# HABduino3_0.net
KiCad netlist of a schematic drawn in EAGLE
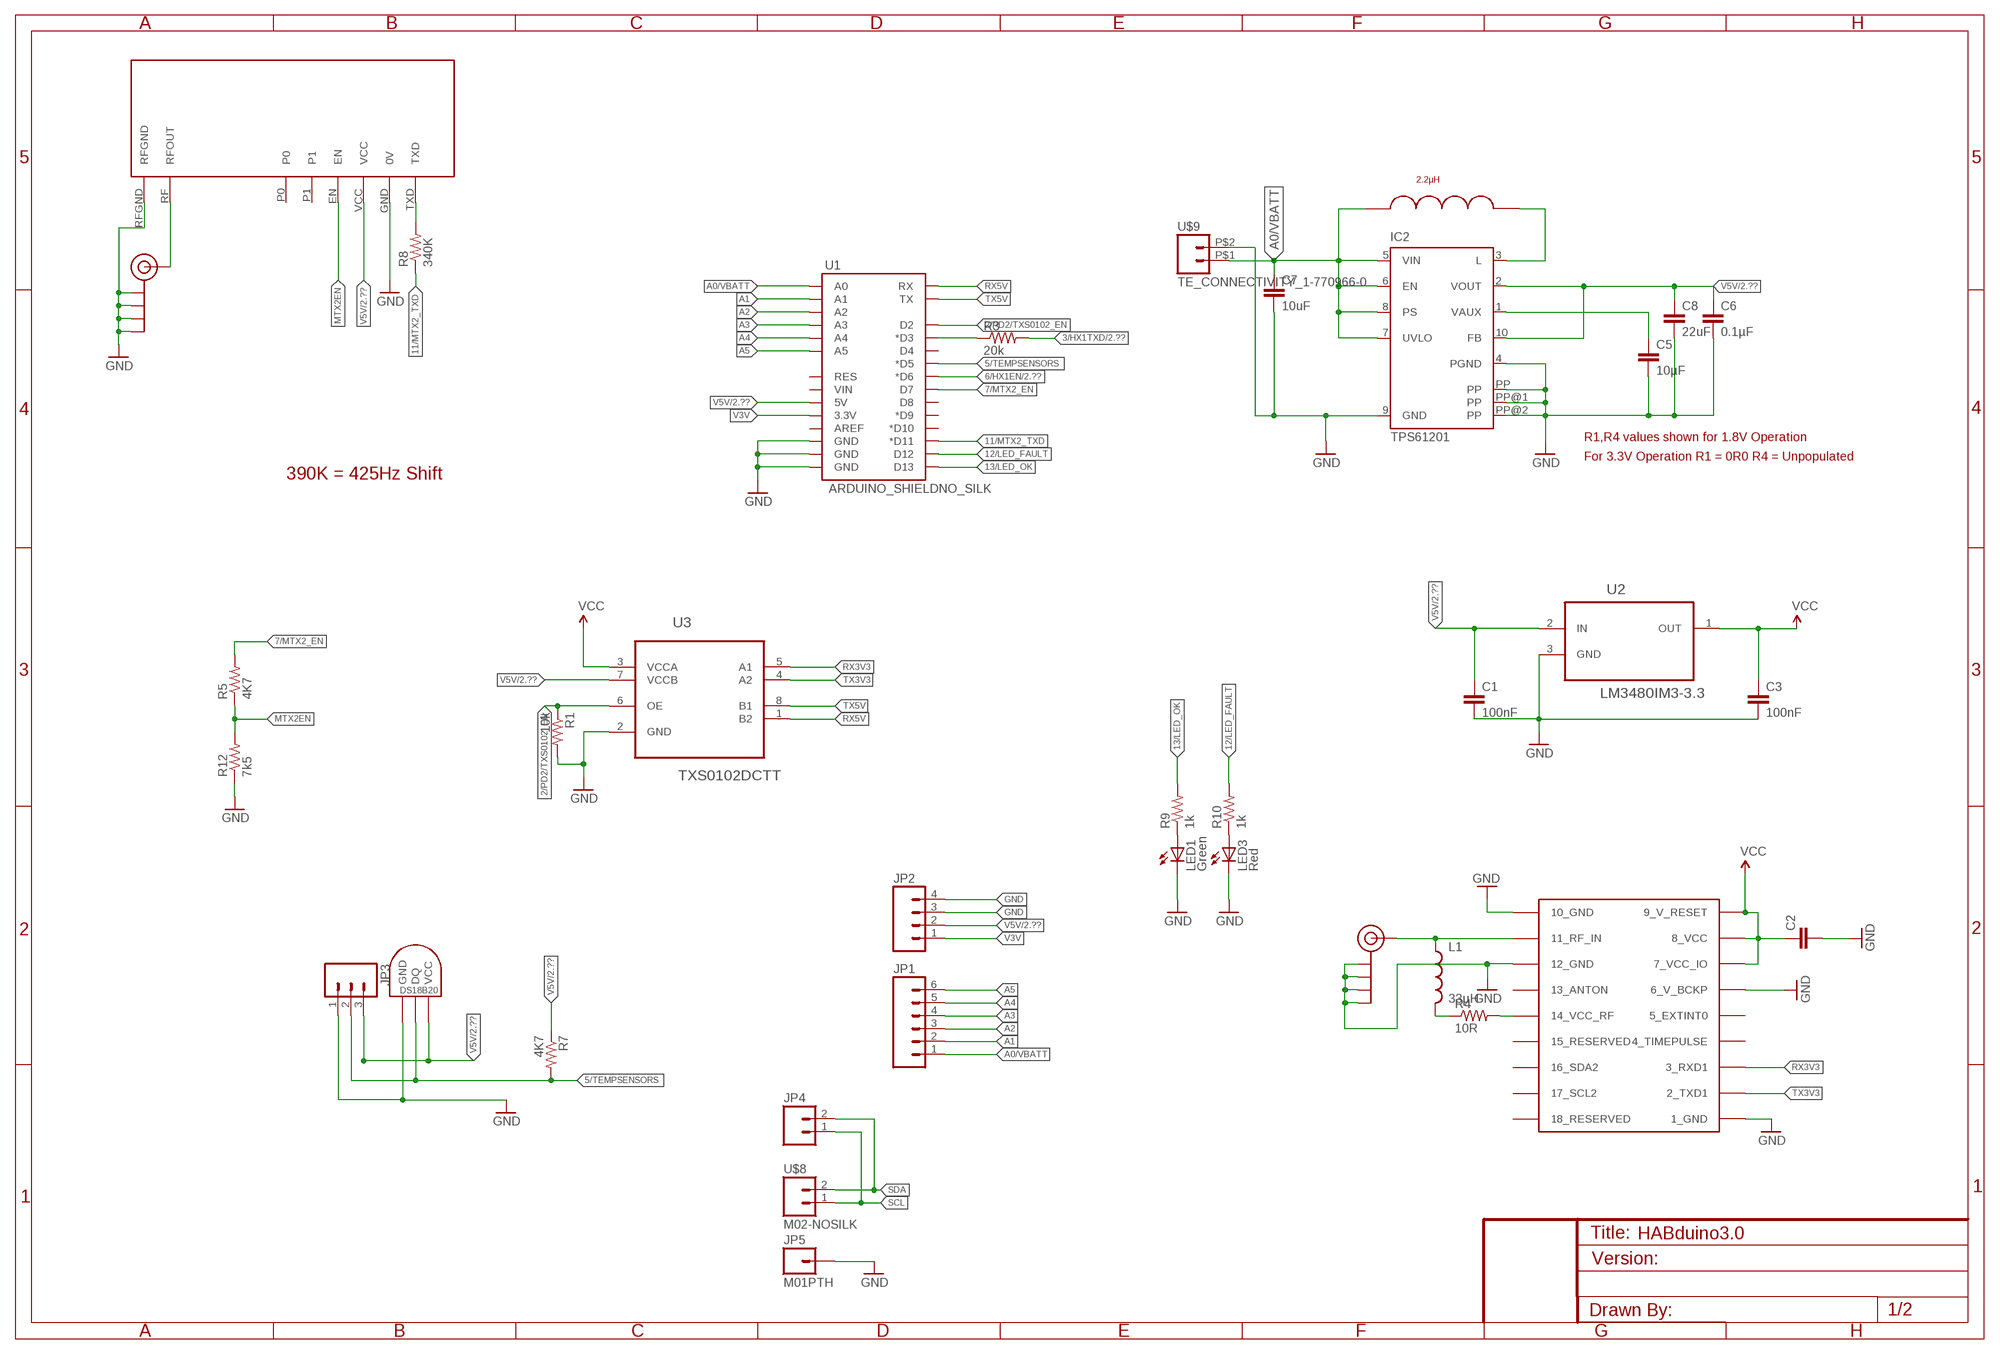
[diagram p0: schematic, sheet 1]
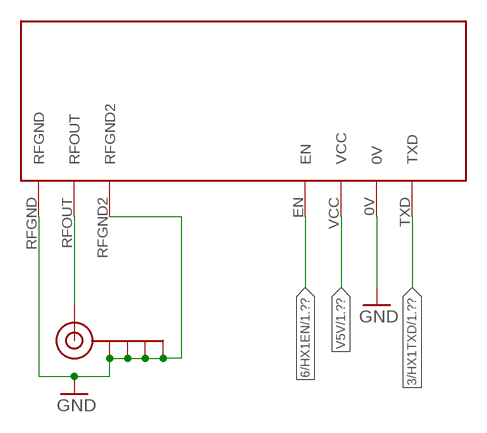
[diagram p1: schematic, sheet 2]

(export (version "E")
  (design (tool "Eeschema 10.0.6"))
  (components
    (comp (ref "J$3")
      (value "SMA_EDGE")
      (footprint "eagle-import:SMA-EDGE")
      (libsource (lib "eagle-import") (part "SMA_EDGE"))
    )
    (comp (ref "U$7")
      (value "RADIOMETRIX-HX1")
      (footprint "eagle-import:RADIOMETRIX-HX1")
      (libsource (lib "eagle-import") (part "RADIOMETRIX-HX1"))
    )
    (comp (ref "C1")
      (value "100nF")
      (footprint "eagle-import:0603-CAP")
      (libsource (lib "eagle-import") (part "CAP0603-CAP"))
    )
    (comp (ref "C2")
      (value "CAP0603-CAP")
      (footprint "eagle-import:0603-CAP")
      (libsource (lib "eagle-import") (part "CAP0603-CAP"))
    )
    (comp (ref "C3")
      (value "100nF")
      (footprint "eagle-import:0603-CAP")
      (libsource (lib "eagle-import") (part "CAP0603-CAP"))
    )
    (comp (ref "C5")
      (value "10µF")
      (footprint "eagle-import:0603-CAP")
      (libsource (lib "eagle-import") (part "CAP0603-CAP"))
    )
    (comp (ref "C6")
      (value "0.1µF")
      (footprint "eagle-import:0603-CAP")
      (libsource (lib "eagle-import") (part "CAP0603-CAP"))
    )
    (comp (ref "C7")
      (value "10uF")
      (footprint "eagle-import:1206")
      (libsource (lib "eagle-import") (part "CAP1206"))
    )
    (comp (ref "C8")
      (value "22uF")
      (footprint "eagle-import:1206")
      (libsource (lib "eagle-import") (part "CAP1206"))
    )
    (comp (ref "IC2")
      (value "TPS61201")
      (footprint "eagle-import:S-PDSO-N10")
      (fields (field (name "MPN") "TPS61201DRCT"))
      (libsource (lib "eagle-import") (part "TPS61201"))
    )
    (comp (ref "J$1")
      (value "SMA_EDGE")
      (footprint "eagle-import:SMA-EDGE")
      (libsource (lib "eagle-import") (part "SMA_EDGE"))
    )
    (comp (ref "J$2")
      (value "SMA_EDGE")
      (footprint "eagle-import:SMA-EDGE")
      (libsource (lib "eagle-import") (part "SMA_EDGE"))
    )
    (comp (ref "JP1")
      (value "M06SIP")
      (footprint "eagle-import:1X06")
      (libsource (lib "eagle-import") (part "M06SIP"))
    )
    (comp (ref "JP2")
      (value "M04PTH")
      (footprint "eagle-import:1X04")
      (libsource (lib "eagle-import") (part "M04PTH"))
    )
    (comp (ref "JP3")
      (value "M03PTH")
      (footprint "eagle-import:1X03")
      (libsource (lib "eagle-import") (part "M03PTH"))
    )
    (comp (ref "JP4")
      (value "M02PTH")
      (footprint "eagle-import:1X02")
      (libsource (lib "eagle-import") (part "M02PTH"))
    )
    (comp (ref "JP5")
      (value "M01PTH")
      (footprint "eagle-import:1X01")
      (libsource (lib "eagle-import") (part "M01PTH"))
    )
    (comp (ref "L1")
      (value "33µH")
      (footprint "eagle-import:0603")
      (libsource (lib "eagle-import") (part "INDUCTOR0603"))
    )
    (comp (ref "LED1")
      (value "Green")
      (footprint "eagle-import:LED-0603")
      (libsource (lib "eagle-import") (part "LED0603"))
    )
    (comp (ref "LED3")
      (value "Red")
      (footprint "eagle-import:LED-0603")
      (libsource (lib "eagle-import") (part "LED0603"))
    )
    (comp (ref "LPS4018")
      (value "2.2µH")
      (footprint "eagle-import:COILCRAFT_LPS4018")
      (libsource (lib "eagle-import") (part "COILCRAFT_LPS4018"))
    )
    (comp (ref "R1")
      (value "10k")
      (footprint "eagle-import:0603-RES")
      (libsource (lib "eagle-import") (part "RESISTOR0603-RES"))
    )
    (comp (ref "R3")
      (value "20k")
      (footprint "eagle-import:0603-RES")
      (libsource (lib "eagle-import") (part "RESISTOR0603-RES"))
    )
    (comp (ref "R4")
      (value "10R")
      (footprint "eagle-import:0603-RES")
      (libsource (lib "eagle-import") (part "RESISTOR0603-RES"))
    )
    (comp (ref "R5")
      (value "4K7")
      (footprint "eagle-import:0603-RES")
      (libsource (lib "eagle-import") (part "RESISTOR0603-RES"))
    )
    (comp (ref "R7")
      (value "4K7")
      (footprint "eagle-import:0603-RES")
      (libsource (lib "eagle-import") (part "RESISTOR0603-RES"))
    )
    (comp (ref "R8")
      (value "340K")
      (footprint "eagle-import:0603-RES")
      (libsource (lib "eagle-import") (part "RESISTOR0603-RES"))
    )
    (comp (ref "R9")
      (value "1k")
      (footprint "eagle-import:0603-RES")
      (libsource (lib "eagle-import") (part "RESISTOR0603-RES"))
    )
    (comp (ref "R10")
      (value "1k")
      (footprint "eagle-import:0603-RES")
      (libsource (lib "eagle-import") (part "RESISTOR0603-RES"))
    )
    (comp (ref "R12")
      (value "7k5")
      (footprint "eagle-import:0603-RES")
      (libsource (lib "eagle-import") (part "RESISTOR0603-RES"))
    )
    (comp (ref "TEMP")
      (value "DS1821")
      (footprint "eagle-import:DS18B20_SOIC")
      (libsource (lib "eagle-import") (part "DS1820SOIC"))
    )
    (comp (ref "U$1")
      (value "UBLOX_MAX")
      (footprint "eagle-import:UBLOX_MAX")
      (libsource (lib "eagle-import") (part "UBLOX_MAX"))
    )
    (comp (ref "U$4")
      (value "RADIOMETRIX-MTX2")
      (footprint "eagle-import:RADIOMETRIX-MTX2")
      (libsource (lib "eagle-import") (part "RADIOMETRIX-MTX2"))
    )
    (comp (ref "U$8")
      (value "M02-NOSILK")
      (footprint "eagle-import:M02-NOSILK")
      (libsource (lib "eagle-import") (part "M02-NOSILK"))
    )
    (comp (ref "U$9")
      (value "TE_CONNECTIVITY_1-770966-0")
      (footprint "eagle-import:TE_CONNECTIVITY_1-770966-0")
      (libsource (lib "eagle-import") (part "TE_CONNECTIVITY_1-770966-0"))
    )
    (comp (ref "U1")
      (value "ARDUINO_SHIELDNO_SILK")
      (footprint "eagle-import:DUEMILANOVE_VIAS")
      (libsource (lib "eagle-import") (part "ARDUINO_SHIELDNO_SILK"))
    )
    (comp (ref "U2")
      (value "LM3480IM3-3.3")
      (footprint "eagle-import:SOT95P251X112-3N")
      (libsource (lib "eagle-import") (part "LM3480IM3-3.3"))
    )
    (comp (ref "U3")
      (value "TXS0102DCTT")
      (footprint "eagle-import:SOP65P400X130-8N")
      (libsource (lib "eagle-import") (part "TXS0102DCTT"))
    )
  )
  (nets
    (net (code "1") (name "2{slash}PD2{slash}TXS0102_EN") (class "Default")
      (node (ref "R1") (pin "1") (pinfunction "1_1") (pintype "passive"))
      (node (ref "U1") (pin "D2") (pinfunction "D2_D2") (pintype "bidirectional"))
      (node (ref "U3") (pin "6") (pinfunction "OE_6") (pintype "input"))
    )
    (net (code "2") (name "3{slash}HX1TXD") (class "Default")
      (node (ref "R3") (pin "2") (pinfunction "2_2") (pintype "passive"))
      (node (ref "U$7") (pin "TXD") (pinfunction "TXD_TXD") (pintype "bidirectional"))
    )
    (net (code "3") (name "5{slash}TEMPSENSORS") (class "Default")
      (node (ref "JP3") (pin "2") (pinfunction "2_2") (pintype "passive"))
      (node (ref "R7") (pin "2") (pinfunction "2_2") (pintype "passive"))
      (node (ref "TEMP") (pin "DQ") (pinfunction "DQ_DQ") (pintype "bidirectional"))
      (node (ref "U1") (pin "D5") (pinfunction "*D5_D5") (pintype "bidirectional"))
    )
    (net (code "4") (name "6{slash}HX1EN") (class "Default")
      (node (ref "U$7") (pin "EN") (pinfunction "EN_EN") (pintype "bidirectional"))
      (node (ref "U1") (pin "D6") (pinfunction "*D6_D6") (pintype "bidirectional"))
    )
    (net (code "5") (name "7{slash}MTX2_EN") (class "Default")
      (node (ref "R5") (pin "2") (pinfunction "2_2") (pintype "passive"))
      (node (ref "U1") (pin "D7") (pinfunction "D7_D7") (pintype "bidirectional"))
    )
    (net (code "6") (name "11{slash}MTX2_TXD") (class "Default")
      (node (ref "R8") (pin "1") (pinfunction "1_1") (pintype "passive"))
      (node (ref "U1") (pin "D11") (pinfunction "*D11_D11") (pintype "bidirectional"))
    )
    (net (code "7") (name "12{slash}LED_FAULT") (class "Default")
      (node (ref "R10") (pin "2") (pinfunction "2_2") (pintype "passive"))
      (node (ref "U1") (pin "D12") (pinfunction "D12_D12") (pintype "bidirectional"))
    )
    (net (code "8") (name "13{slash}LED_OK") (class "Default")
      (node (ref "R9") (pin "2") (pinfunction "2_2") (pintype "passive"))
      (node (ref "U1") (pin "D13") (pinfunction "D13_D13") (pintype "bidirectional"))
    )
    (net (code "9") (name "A0{slash}VBATT") (class "Default")
      (node (ref "C7") (pin "1") (pinfunction "1_1") (pintype "passive"))
      (node (ref "IC2") (pin "5") (pinfunction "VIN_5") (pintype "input"))
      (node (ref "IC2") (pin "6") (pinfunction "EN_6") (pintype "input"))
      (node (ref "IC2") (pin "7") (pinfunction "UVLO_7") (pintype "input"))
      (node (ref "IC2") (pin "8") (pinfunction "PS_8") (pintype "input"))
      (node (ref "JP1") (pin "1") (pinfunction "1_1") (pintype "passive"))
      (node (ref "LPS4018") (pin "P$1") (pinfunction "P$1_P$1") (pintype "bidirectional"))
      (node (ref "U$9") (pin "P$1") (pinfunction "1_P$1") (pintype "passive"))
      (node (ref "U1") (pin "A0") (pinfunction "A0_A0") (pintype "bidirectional"))
    )
    (net (code "10") (name "A1") (class "Default")
      (node (ref "JP1") (pin "2") (pinfunction "2_2") (pintype "passive"))
      (node (ref "U1") (pin "A1") (pinfunction "A1_A1") (pintype "bidirectional"))
    )
    (net (code "11") (name "A2") (class "Default")
      (node (ref "JP1") (pin "3") (pinfunction "3_3") (pintype "passive"))
      (node (ref "U1") (pin "A2") (pinfunction "A2_A2") (pintype "bidirectional"))
    )
    (net (code "12") (name "A3") (class "Default")
      (node (ref "JP1") (pin "4") (pinfunction "4_4") (pintype "passive"))
      (node (ref "U1") (pin "A3") (pinfunction "A3_A3") (pintype "bidirectional"))
    )
    (net (code "13") (name "A4") (class "Default")
      (node (ref "JP1") (pin "5") (pinfunction "5_5") (pintype "passive"))
      (node (ref "U1") (pin "A4") (pinfunction "A4_A4") (pintype "bidirectional"))
    )
    (net (code "14") (name "A5") (class "Default")
      (node (ref "JP1") (pin "6") (pinfunction "6_6") (pintype "passive"))
      (node (ref "U1") (pin "A5") (pinfunction "A5_A5") (pintype "bidirectional"))
    )
    (net (code "15") (name "GND") (class "Default")
      (node (ref "C1") (pin "2") (pinfunction "2_2") (pintype "passive"))
      (node (ref "C2") (pin "2") (pinfunction "2_2") (pintype "passive"))
      (node (ref "C3") (pin "2") (pinfunction "2_2") (pintype "passive"))
      (node (ref "C5") (pin "2") (pinfunction "2_2") (pintype "passive"))
      (node (ref "C6") (pin "2") (pinfunction "2_2") (pintype "passive"))
      (node (ref "C7") (pin "2") (pinfunction "2_2") (pintype "passive"))
      (node (ref "C8") (pin "2") (pinfunction "2_2") (pintype "passive"))
      (node (ref "IC2") (pin "4") (pinfunction "PGND_4") (pintype "power_in"))
      (node (ref "IC2") (pin "9") (pinfunction "GND_9") (pintype "power_in"))
      (node (ref "IC2") (pin "PP") (pinfunction "PP_PP") (pintype "power_in"))
      (node (ref "IC2") (pin "PP@1") (pinfunction "PP_PP@1") (pintype "power_in"))
      (node (ref "IC2") (pin "PP@2") (pinfunction "PP_PP@2") (pintype "power_in"))
      (node (ref "J$1") (pin "GND@0") (pinfunction "GND_GND@0") (pintype "bidirectional"))
      (node (ref "J$1") (pin "GND@1") (pinfunction "GND_GND@1") (pintype "bidirectional"))
      (node (ref "J$1") (pin "GND@2") (pinfunction "GND_GND@2") (pintype "bidirectional"))
      (node (ref "J$1") (pin "GND@3") (pinfunction "GND_GND@3") (pintype "bidirectional"))
      (node (ref "J$2") (pin "GND@0") (pinfunction "GND_GND@0") (pintype "bidirectional"))
      (node (ref "J$2") (pin "GND@1") (pinfunction "GND_GND@1") (pintype "bidirectional"))
      (node (ref "J$2") (pin "GND@2") (pinfunction "GND_GND@2") (pintype "bidirectional"))
      (node (ref "J$2") (pin "GND@3") (pinfunction "GND_GND@3") (pintype "bidirectional"))
      (node (ref "J$3") (pin "GND@0") (pinfunction "GND_GND@0") (pintype "bidirectional"))
      (node (ref "J$3") (pin "GND@1") (pinfunction "GND_GND@1") (pintype "bidirectional"))
      (node (ref "J$3") (pin "GND@2") (pinfunction "GND_GND@2") (pintype "bidirectional"))
      (node (ref "J$3") (pin "GND@3") (pinfunction "GND_GND@3") (pintype "bidirectional"))
      (node (ref "JP2") (pin "3") (pinfunction "3_3") (pintype "passive"))
      (node (ref "JP2") (pin "4") (pinfunction "4_4") (pintype "passive"))
      (node (ref "JP3") (pin "1") (pinfunction "1_1") (pintype "passive"))
      (node (ref "JP5") (pin "1") (pinfunction "1_1") (pintype "passive"))
      (node (ref "LED1") (pin "C") (pinfunction "C_C") (pintype "passive"))
      (node (ref "LED3") (pin "C") (pinfunction "C_C") (pintype "passive"))
      (node (ref "R1") (pin "2") (pinfunction "2_2") (pintype "passive"))
      (node (ref "R12") (pin "1") (pinfunction "1_1") (pintype "passive"))
      (node (ref "TEMP") (pin "GND") (pinfunction "GND_GND") (pintype "power_in"))
      (node (ref "U$1") (pin "10_GND") (pinfunction "10_GND_10_GND") (pintype "power_in"))
      (node (ref "U$1") (pin "12_GND") (pinfunction "12_GND_12_GND") (pintype "power_in"))
      (node (ref "U$1") (pin "1_GND") (pinfunction "1_GND_1_GND") (pintype "power_in"))
      (node (ref "U$1") (pin "6_V_BCKP") (pinfunction "6_V_BCKP_6_V_BCKP") (pintype "bidirectional"))
      (node (ref "U$4") (pin "GND") (pinfunction "0V_GND") (pintype "bidirectional"))
      (node (ref "U$4") (pin "RFGND") (pinfunction "RFGND_RFGND") (pintype "bidirectional"))
      (node (ref "U$7") (pin "0V") (pinfunction "0V_0V") (pintype "bidirectional"))
      (node (ref "U$7") (pin "RFGND") (pinfunction "RFGND_RFGND") (pintype "bidirectional"))
      (node (ref "U$7") (pin "RFGND2") (pinfunction "RFGND2_RFGND2") (pintype "bidirectional"))
      (node (ref "U$9") (pin "P$2") (pinfunction "2_P$2") (pintype "passive"))
      (node (ref "U1") (pin "GND@0") (pinfunction "GND_GND@0") (pintype "bidirectional"))
      (node (ref "U1") (pin "GND@1") (pinfunction "GND_GND@1") (pintype "bidirectional"))
      (node (ref "U1") (pin "GND@2") (pinfunction "GND_GND@2") (pintype "bidirectional"))
      (node (ref "U2") (pin "3") (pinfunction "GND_3") (pintype "passive"))
      (node (ref "U3") (pin "2") (pinfunction "GND_2") (pintype "passive"))
    )
    (net (code "16") (name "MTX2EN") (class "Default")
      (node (ref "R12") (pin "2") (pinfunction "2_2") (pintype "passive"))
      (node (ref "R5") (pin "1") (pinfunction "1_1") (pintype "passive"))
      (node (ref "U$4") (pin "EN") (pinfunction "EN_EN") (pintype "bidirectional"))
    )
    (net (code "17") (name "Net-(IC2-L)") (class "Default")
      (node (ref "IC2") (pin "3") (pinfunction "L_3") (pintype "input"))
      (node (ref "LPS4018") (pin "P$2") (pinfunction "P$2_P$2") (pintype "bidirectional"))
    )
    (net (code "18") (name "Net-(IC2-VAUX)") (class "Default")
      (node (ref "C5") (pin "1") (pinfunction "1_1") (pintype "passive"))
      (node (ref "IC2") (pin "1") (pinfunction "VAUX_1") (pintype "bidirectional"))
    )
    (net (code "19") (name "Net-(J$1-SIGNAL)") (class "Default")
      (node (ref "J$1") (pin "SIG") (pinfunction "SIGNAL_SIG") (pintype "bidirectional"))
      (node (ref "U$4") (pin "RF") (pinfunction "RFOUT_RF") (pintype "bidirectional"))
    )
    (net (code "20") (name "Net-(J$2-SIGNAL)") (class "Default")
      (node (ref "J$2") (pin "SIG") (pinfunction "SIGNAL_SIG") (pintype "bidirectional"))
      (node (ref "L1") (pin "1") (pinfunction "1_1") (pintype "passive"))
      (node (ref "U$1") (pin "11_RF_IN") (pinfunction "11_RF_IN_11_RF_IN") (pintype "bidirectional"))
    )
    (net (code "21") (name "Net-(J$3-SIGNAL)") (class "Default")
      (node (ref "J$3") (pin "SIG") (pinfunction "SIGNAL_SIG") (pintype "bidirectional"))
      (node (ref "U$7") (pin "RFOUT") (pinfunction "RFOUT_RFOUT") (pintype "bidirectional"))
    )
    (net (code "22") (name "Net-(L1-Pad2)") (class "Default")
      (node (ref "L1") (pin "2") (pinfunction "2_2") (pintype "passive"))
      (node (ref "R4") (pin "1") (pinfunction "1_1") (pintype "passive"))
    )
    (net (code "23") (name "Net-(LED1-PadA)") (class "Default")
      (node (ref "LED1") (pin "A") (pinfunction "A_A") (pintype "passive"))
      (node (ref "R9") (pin "1") (pinfunction "1_1") (pintype "passive"))
    )
    (net (code "24") (name "Net-(LED3-PadA)") (class "Default")
      (node (ref "LED3") (pin "A") (pinfunction "A_A") (pintype "passive"))
      (node (ref "R10") (pin "1") (pinfunction "1_1") (pintype "passive"))
    )
    (net (code "25") (name "Net-(R4-Pad2)") (class "Default")
      (node (ref "R4") (pin "2") (pinfunction "2_2") (pintype "passive"))
      (node (ref "U$1") (pin "14_VCC_RF") (pinfunction "14_VCC_RF_14_VCC_RF") (pintype "bidirectional"))
    )
    (net (code "26") (name "Net-(R8-Pad2)") (class "Default")
      (node (ref "R8") (pin "2") (pinfunction "2_2") (pintype "passive"))
      (node (ref "U$4") (pin "TXD") (pinfunction "TXD_TXD") (pintype "bidirectional"))
    )
    (net (code "27") (name "Net-(U1-*D3)") (class "Default")
      (node (ref "R3") (pin "1") (pinfunction "1_1") (pintype "passive"))
      (node (ref "U1") (pin "D3") (pinfunction "*D3_D3") (pintype "bidirectional"))
    )
    (net (code "28") (name "RX3V3") (class "Default")
      (node (ref "U$1") (pin "3_RXD1") (pinfunction "3_RXD1_3_RXD1") (pintype "bidirectional"))
      (node (ref "U3") (pin "5") (pinfunction "A1_5") (pintype "bidirectional"))
    )
    (net (code "29") (name "RX5V") (class "Default")
      (node (ref "U1") (pin "RX") (pinfunction "RX_RX") (pintype "bidirectional"))
      (node (ref "U3") (pin "1") (pinfunction "B2_1") (pintype "bidirectional"))
    )
    (net (code "30") (name "SCL") (class "Default")
      (node (ref "JP4") (pin "1") (pinfunction "1_1") (pintype "passive"))
      (node (ref "U$8") (pin "1") (pinfunction "1_1") (pintype "passive"))
    )
    (net (code "31") (name "SDA") (class "Default")
      (node (ref "JP4") (pin "2") (pinfunction "2_2") (pintype "passive"))
      (node (ref "U$8") (pin "2") (pinfunction "2_2") (pintype "passive"))
    )
    (net (code "32") (name "TX3V3") (class "Default")
      (node (ref "U$1") (pin "2_TXD1") (pinfunction "2_TXD1_2_TXD1") (pintype "bidirectional"))
      (node (ref "U3") (pin "4") (pinfunction "A2_4") (pintype "bidirectional"))
    )
    (net (code "33") (name "TX5V") (class "Default")
      (node (ref "U1") (pin "TX") (pinfunction "TX_TX") (pintype "bidirectional"))
      (node (ref "U3") (pin "8") (pinfunction "B1_8") (pintype "bidirectional"))
    )
    (net (code "34") (name "V3V") (class "Default")
      (node (ref "JP2") (pin "1") (pinfunction "1_1") (pintype "passive"))
      (node (ref "U1") (pin "3.3V") (pinfunction "3.3V_3.3V") (pintype "bidirectional"))
    )
    (net (code "35") (name "V5V") (class "Default")
      (node (ref "C1") (pin "1") (pinfunction "1_1") (pintype "passive"))
      (node (ref "C6") (pin "1") (pinfunction "1_1") (pintype "passive"))
      (node (ref "C8") (pin "1") (pinfunction "1_1") (pintype "passive"))
      (node (ref "IC2") (pin "10") (pinfunction "FB_10") (pintype "input"))
      (node (ref "IC2") (pin "2") (pinfunction "VOUT_2") (pintype "passive"))
      (node (ref "JP2") (pin "2") (pinfunction "2_2") (pintype "passive"))
      (node (ref "JP3") (pin "3") (pinfunction "3_3") (pintype "passive"))
      (node (ref "R7") (pin "1") (pinfunction "1_1") (pintype "passive"))
      (node (ref "TEMP") (pin "VCC") (pinfunction "VCC_VCC") (pintype "power_in"))
      (node (ref "U$4") (pin "VCC") (pinfunction "VCC_VCC") (pintype "bidirectional"))
      (node (ref "U$7") (pin "VCC") (pinfunction "VCC_VCC") (pintype "bidirectional"))
      (node (ref "U1") (pin "5V") (pinfunction "5V_5V") (pintype "bidirectional"))
      (node (ref "U2") (pin "2") (pinfunction "IN_2") (pintype "power_in"))
      (node (ref "U3") (pin "7") (pinfunction "VCCB_7") (pintype "power_in"))
    )
    (net (code "36") (name "VCC") (class "Default")
      (node (ref "C2") (pin "1") (pinfunction "1_1") (pintype "passive"))
      (node (ref "C3") (pin "1") (pinfunction "1_1") (pintype "passive"))
      (node (ref "U$1") (pin "7_VCC_IO") (pinfunction "7_VCC_IO_7_VCC_IO") (pintype "power_in"))
      (node (ref "U$1") (pin "8_VCC") (pinfunction "8_VCC_8_VCC") (pintype "power_in"))
      (node (ref "U$1") (pin "9_V_RESET") (pinfunction "9_V_RESET_9_V_RESET") (pintype "power_in"))
      (node (ref "U2") (pin "1") (pinfunction "OUT_1") (pintype "output"))
      (node (ref "U3") (pin "3") (pinfunction "VCCA_3") (pintype "power_in"))
    )
    (net (code "37") (name "unconnected-(U$1-Pad4_TIMEPULSE)") (class "Default")
      (node (ref "U$1") (pin "4_TIMEPULSE") (pinfunction "4_TIMEPULSE_4_TIMEPULSE") (pintype "bidirectional"))
    )
    (net (code "38") (name "unconnected-(U$1-Pad5_EXTINT0)") (class "Default")
      (node (ref "U$1") (pin "5_EXTINT0") (pinfunction "5_EXTINT0_5_EXTINT0") (pintype "bidirectional"))
    )
    (net (code "39") (name "unconnected-(U$1-Pad13_ANTON)") (class "Default")
      (node (ref "U$1") (pin "13_ANTON") (pinfunction "13_ANTON_13_ANTON") (pintype "bidirectional"))
    )
    (net (code "40") (name "unconnected-(U$1-Pad15_RESERVED)") (class "Default")
      (node (ref "U$1") (pin "15_RESERVED") (pinfunction "15_RESERVED_15_RESERVED") (pintype "bidirectional"))
    )
    (net (code "41") (name "unconnected-(U$1-Pad16_SDA2)") (class "Default")
      (node (ref "U$1") (pin "16_SDA2") (pinfunction "16_SDA2_16_SDA2") (pintype "bidirectional"))
    )
    (net (code "42") (name "unconnected-(U$1-Pad17_SCL2)") (class "Default")
      (node (ref "U$1") (pin "17_SCL2") (pinfunction "17_SCL2_17_SCL2") (pintype "bidirectional"))
    )
    (net (code "43") (name "unconnected-(U$1-Pad18_RESERVED)") (class "Default")
      (node (ref "U$1") (pin "18_RESERVED") (pinfunction "18_RESERVED_18_RESERVED") (pintype "bidirectional"))
    )
    (net (code "44") (name "unconnected-(U$4-PadP0)") (class "Default")
      (node (ref "U$4") (pin "P0") (pinfunction "P0_P0") (pintype "bidirectional"))
    )
    (net (code "45") (name "unconnected-(U$4-PadP1)") (class "Default")
      (node (ref "U$4") (pin "P1") (pinfunction "P1_P1") (pintype "bidirectional"))
    )
    (net (code "46") (name "unconnected-(U1-*D9-PadD9)") (class "Default")
      (node (ref "U1") (pin "D9") (pinfunction "*D9_D9") (pintype "bidirectional"))
    )
    (net (code "47") (name "unconnected-(U1-*D10-PadD10)") (class "Default")
      (node (ref "U1") (pin "D10") (pinfunction "*D10_D10") (pintype "bidirectional"))
    )
    (net (code "48") (name "unconnected-(U1-PadAREF)") (class "Default")
      (node (ref "U1") (pin "AREF") (pinfunction "AREF_AREF") (pintype "bidirectional"))
    )
    (net (code "49") (name "unconnected-(U1-PadD4)") (class "Default")
      (node (ref "U1") (pin "D4") (pinfunction "D4_D4") (pintype "bidirectional"))
    )
    (net (code "50") (name "unconnected-(U1-PadD8)") (class "Default")
      (node (ref "U1") (pin "D8") (pinfunction "D8_D8") (pintype "bidirectional"))
    )
    (net (code "51") (name "unconnected-(U1-PadRES)") (class "Default")
      (node (ref "U1") (pin "RES") (pinfunction "RES_RES") (pintype "bidirectional"))
    )
    (net (code "52") (name "unconnected-(U1-PadVIN)") (class "Default")
      (node (ref "U1") (pin "VIN") (pinfunction "VIN_VIN") (pintype "bidirectional"))
    )
  )
)
